# DaisyChainv2.net
KiCad netlist of a schematic drawn in EAGLE
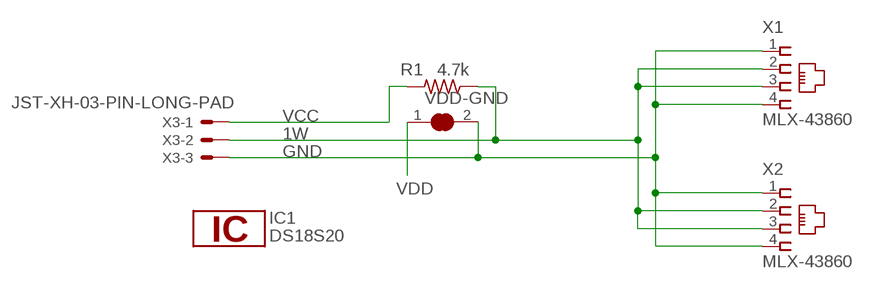
[diagram p0: schematic, sheet 1]

(export (version "E")
  (design (tool "Eeschema 10.0.6"))
  (components
    (comp (ref "IC1")
      (value "DS18S20")
      (footprint "eagle-import:TO92-")
      (libsource (lib "eagle-import") (part "DS18S20"))
    )
    (comp (ref "R1")
      (value "4.7k")
      (footprint "eagle-import:0207_10")
      (libsource (lib "eagle-import") (part "R-US_0207/10"))
    )
    (comp (ref "VDD-GND")
      (value "SJW-SHORTED")
      (footprint "eagle-import:SJW-SHORTED")
      (libsource (lib "eagle-import") (part "SJW-SHORTED"))
    )
    (comp (ref "X1")
      (value "MLX-43860")
      (footprint "eagle-import:MLX-43860")
      (fields (field (name "MF") "MOLEX"))
      (libsource (lib "eagle-import") (part "MLX-43860"))
    )
    (comp (ref "X2")
      (value "MLX-43860")
      (footprint "eagle-import:MLX-43860")
      (fields (field (name "MF") "MOLEX"))
      (libsource (lib "eagle-import") (part "MLX-43860"))
    )
    (comp (ref "X3")
      (value "JST-XH-03-PIN-LONG-PAD")
      (footprint "eagle-import:JST-XH-03-PACKAGE-LONG-PAD")
      (libsource (lib "eagle-import") (part "JST-XH-03-PIN-LONG-PAD"))
    )
  )
  (nets
    (net (code "1") (name "/1W") (class "Default")
      (node (ref "R1") (pin "1") (pinfunction "1_1") (pintype "passive"))
      (node (ref "X1") (pin "2") (pinfunction "2_2") (pintype "passive"))
      (node (ref "X1") (pin "3") (pinfunction "3_3") (pintype "passive"))
      (node (ref "X2") (pin "2") (pinfunction "2_2") (pintype "passive"))
      (node (ref "X2") (pin "3") (pinfunction "3_3") (pintype "passive"))
      (node (ref "X3") (pin "2") (pinfunction "S_2") (pintype "passive"))
    )
    (net (code "2") (name "/GND") (class "Default")
      (node (ref "VDD-GND") (pin "2") (pinfunction "2_2") (pintype "passive"))
      (node (ref "X1") (pin "1") (pinfunction "1_1") (pintype "passive"))
      (node (ref "X1") (pin "4") (pinfunction "4_4") (pintype "passive"))
      (node (ref "X2") (pin "1") (pinfunction "1_1") (pintype "passive"))
      (node (ref "X2") (pin "4") (pinfunction "4_4") (pintype "passive"))
      (node (ref "X3") (pin "3") (pinfunction "S_3") (pintype "passive"))
    )
    (net (code "3") (name "/VCC") (class "Default")
      (node (ref "R1") (pin "2") (pinfunction "2_2") (pintype "passive"))
      (node (ref "X3") (pin "1") (pinfunction "S_1") (pintype "passive"))
    )
    (net (code "4") (name "/VDD") (class "Default")
      (node (ref "VDD-GND") (pin "1") (pinfunction "1_1") (pintype "passive"))
    )
  )
)
